# source_eagle.net
KiCad netlist of a schematic drawn in EAGLE
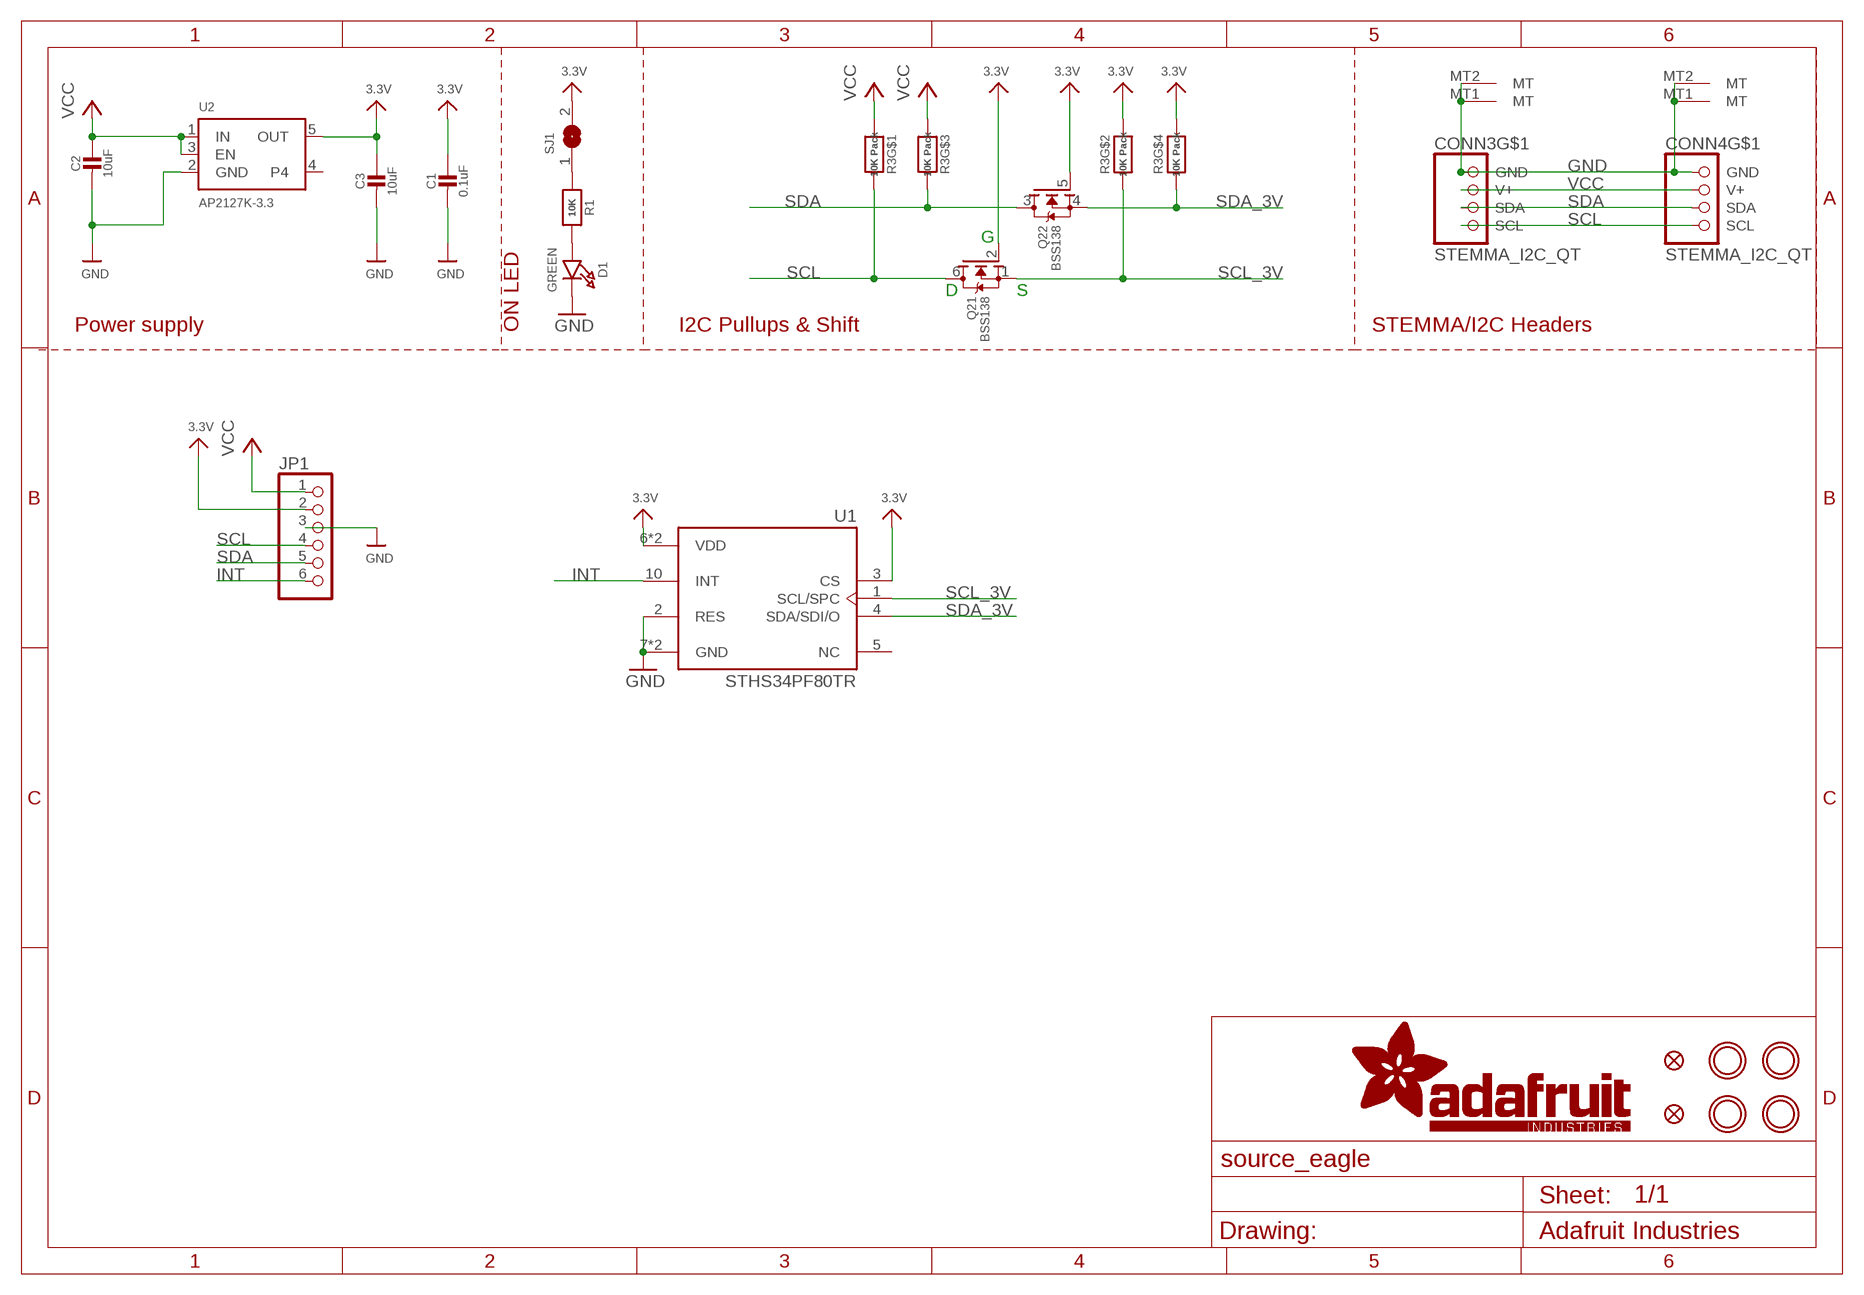
[diagram p0: schematic, sheet 1]

(export (version "E")
  (design (tool "Eeschema 10.0.6"))
  (components
    (comp (ref "C1")
      (value "0.1uF")
      (footprint "eagle-import:0603-NO")
      (libsource (lib "eagle-import") (part "CAP_CERAMIC0603_NO"))
    )
    (comp (ref "C2")
      (value "10uF")
      (footprint "eagle-import:0805-NO")
      (libsource (lib "eagle-import") (part "CAP_CERAMIC0805-NOOUTLINE"))
    )
    (comp (ref "C3")
      (value "10uF")
      (footprint "eagle-import:0805-NO")
      (libsource (lib "eagle-import") (part "CAP_CERAMIC0805-NOOUTLINE"))
    )
    (comp (ref "CONN3")
      (value "STEMMA_I2C_QT")
      (footprint "eagle-import:JST_SH4")
      (libsource (lib "eagle-import") (part "STEMMA_I2C_QT"))
    )
    (comp (ref "CONN4")
      (value "STEMMA_I2C_QT")
      (footprint "eagle-import:JST_SH4")
      (libsource (lib "eagle-import") (part "STEMMA_I2C_QT"))
    )
    (comp (ref "D1")
      (value "GREEN")
      (footprint "eagle-import:CHIPLED_0603_NOOUTLINE")
      (libsource (lib "eagle-import") (part "LED0603_NOOUTLINE"))
    )
    (comp (ref "FID3")
      (value "FIDUCIAL_0.5MM")
      (footprint "eagle-import:FIDUCIAL_0.5MM")
      (libsource (lib "eagle-import") (part "FIDUCIAL_0.5MM"))
    )
    (comp (ref "FID4")
      (value "FIDUCIAL_0.5MM")
      (footprint "eagle-import:FIDUCIAL_0.5MM")
      (libsource (lib "eagle-import") (part "FIDUCIAL_0.5MM"))
    )
    (comp (ref "JP1")
      (value "HEADER-1X670MIL")
      (footprint "eagle-import:1X06_ROUND_70")
      (libsource (lib "eagle-import") (part "HEADER-1X670MIL"))
    )
    (comp (ref "Q2")
      (value "BSS138")
      (footprint "eagle-import:SOT363")
      (libsource (lib "eagle-import") (part "MOSFET-N_DUAL"))
    )
    (comp (ref "R1")
      (value "10K")
      (footprint "eagle-import:0603-NO")
      (libsource (lib "eagle-import") (part "RESISTOR_0603_NOOUT"))
    )
    (comp (ref "R3")
      (value "10K Pack")
      (footprint "eagle-import:RESPACK_4X0603")
      (libsource (lib "eagle-import") (part "RESISTOR_4PACK"))
    )
    (comp (ref "SJ1")
      (value "SOLDERJUMPERCLOSED")
      (footprint "eagle-import:SOLDERJUMPER_CLOSEDWIRE")
      (libsource (lib "eagle-import") (part "SOLDERJUMPERCLOSED"))
    )
    (comp (ref "U$1")
      (value "MOUNTINGHOLE2.5")
      (footprint "eagle-import:MOUNTINGHOLE_2.5_PLATED")
      (libsource (lib "eagle-import") (part "MOUNTINGHOLE2.5"))
    )
    (comp (ref "U$17")
      (value "MOUNTINGHOLE2.5")
      (footprint "eagle-import:MOUNTINGHOLE_2.5_PLATED")
      (libsource (lib "eagle-import") (part "MOUNTINGHOLE2.5"))
    )
    (comp (ref "U$19")
      (value "MOUNTINGHOLE2.5")
      (footprint "eagle-import:MOUNTINGHOLE_2.5_PLATED")
      (libsource (lib "eagle-import") (part "MOUNTINGHOLE2.5"))
    )
    (comp (ref "U$21")
      (value "MOUNTINGHOLE2.5")
      (footprint "eagle-import:MOUNTINGHOLE_2.5_PLATED")
      (libsource (lib "eagle-import") (part "MOUNTINGHOLE2.5"))
    )
    (comp (ref "U1")
      (value "STHS34PF80TR")
      (footprint "eagle-import:XDCR_STHS34PF80TR")
      (fields (field (name "MANUFACTURER") "STmicroelectronics"))
      (libsource (lib "eagle-import") (part "STHS34PF80TR"))
    )
    (comp (ref "U2")
      (value "AP2127K-3.3")
      (footprint "eagle-import:SOT23-5")
      (libsource (lib "eagle-import") (part "VREG_SOT23-5"))
    )
  )
  (nets
    (net (code "1") (name "/INT") (class "Default")
      (node (ref "JP1") (pin "6") (pinfunction "6_6") (pintype "passive"))
      (node (ref "U1") (pin "10") (pinfunction "INT_10") (pintype "output"))
    )
    (net (code "2") (name "/SCL") (class "Default")
      (node (ref "CONN3") (pin "4") (pinfunction "SCL_4") (pintype "passive"))
      (node (ref "CONN4") (pin "4") (pinfunction "SCL_4") (pintype "passive"))
      (node (ref "JP1") (pin "4") (pinfunction "4_4") (pintype "passive"))
      (node (ref "Q2") (pin "6") (pinfunction "D_6") (pintype "bidirectional"))
      (node (ref "R3") (pin "8") (pinfunction "2_8") (pintype "passive"))
    )
    (net (code "3") (name "/SCL_3V") (class "Default")
      (node (ref "Q2") (pin "1") (pinfunction "S_1") (pintype "bidirectional"))
      (node (ref "R3") (pin "7") (pinfunction "2_7") (pintype "passive"))
      (node (ref "U1") (pin "1") (pinfunction "SCL/SPC_1") (pintype "input"))
    )
    (net (code "4") (name "/SDA") (class "Default")
      (node (ref "CONN3") (pin "3") (pinfunction "SDA_3") (pintype "passive"))
      (node (ref "CONN4") (pin "3") (pinfunction "SDA_3") (pintype "passive"))
      (node (ref "JP1") (pin "5") (pinfunction "5_5") (pintype "passive"))
      (node (ref "Q2") (pin "3") (pinfunction "D_3") (pintype "bidirectional"))
      (node (ref "R3") (pin "6") (pinfunction "2_6") (pintype "passive"))
    )
    (net (code "5") (name "/SDA_3V") (class "Default")
      (node (ref "Q2") (pin "4") (pinfunction "S_4") (pintype "bidirectional"))
      (node (ref "R3") (pin "5") (pinfunction "2_5") (pintype "passive"))
      (node (ref "U1") (pin "4") (pinfunction "SDA/SDI/O_4") (pintype "bidirectional"))
    )
    (net (code "6") (name "3.3V") (class "Default")
      (node (ref "C1") (pin "1") (pinfunction "1_1") (pintype "passive"))
      (node (ref "C3") (pin "1") (pinfunction "1_1") (pintype "passive"))
      (node (ref "JP1") (pin "2") (pinfunction "2_2") (pintype "passive"))
      (node (ref "Q2") (pin "2") (pinfunction "G_2") (pintype "bidirectional"))
      (node (ref "Q2") (pin "5") (pinfunction "G_5") (pintype "bidirectional"))
      (node (ref "R3") (pin "2") (pinfunction "1_2") (pintype "passive"))
      (node (ref "R3") (pin "4") (pinfunction "1_4") (pintype "passive"))
      (node (ref "SJ1") (pin "2") (pinfunction "2_2") (pintype "passive"))
      (node (ref "U1") (pin "3") (pinfunction "CS_3") (pintype "input"))
      (node (ref "U1") (pin "6") (pinfunction "VDD_6") (pintype "power_in"))
      (node (ref "U1") (pin "9") (pinfunction "VDD_9") (pintype "power_in"))
      (node (ref "U2") (pin "5") (pinfunction "OUT_5") (pintype "power_in"))
    )
    (net (code "7") (name "GND") (class "Default")
      (node (ref "C1") (pin "2") (pinfunction "2_2") (pintype "passive"))
      (node (ref "C2") (pin "2") (pinfunction "2_2") (pintype "passive"))
      (node (ref "C3") (pin "2") (pinfunction "2_2") (pintype "passive"))
      (node (ref "CONN3") (pin "1") (pinfunction "GND_1") (pintype "passive"))
      (node (ref "CONN3") (pin "MT1") (pinfunction "MT_MT1") (pintype "bidirectional"))
      (node (ref "CONN3") (pin "MT2") (pinfunction "MT_MT2") (pintype "bidirectional"))
      (node (ref "CONN4") (pin "1") (pinfunction "GND_1") (pintype "passive"))
      (node (ref "CONN4") (pin "MT1") (pinfunction "MT_MT1") (pintype "bidirectional"))
      (node (ref "CONN4") (pin "MT2") (pinfunction "MT_MT2") (pintype "bidirectional"))
      (node (ref "D1") (pin "C") (pinfunction "C_C") (pintype "passive"))
      (node (ref "JP1") (pin "3") (pinfunction "3_3") (pintype "passive"))
      (node (ref "U1") (pin "2") (pinfunction "RES_2") (pintype "passive"))
      (node (ref "U1") (pin "7") (pinfunction "GND_7") (pintype "power_in"))
      (node (ref "U1") (pin "8") (pinfunction "GND_8") (pintype "power_in"))
      (node (ref "U2") (pin "2") (pinfunction "GND_2") (pintype "power_in"))
    )
    (net (code "8") (name "Net-(D1-PadA)") (class "Default")
      (node (ref "D1") (pin "A") (pinfunction "A_A") (pintype "passive"))
      (node (ref "R1") (pin "2") (pinfunction "2_2") (pintype "passive"))
    )
    (net (code "9") (name "Net-(R1-Pad1)") (class "Default")
      (node (ref "R1") (pin "1") (pinfunction "1_1") (pintype "passive"))
      (node (ref "SJ1") (pin "1") (pinfunction "1_1") (pintype "passive"))
    )
    (net (code "10") (name "VCC") (class "Default")
      (node (ref "C2") (pin "1") (pinfunction "1_1") (pintype "passive"))
      (node (ref "CONN3") (pin "2") (pinfunction "V+_2") (pintype "passive"))
      (node (ref "CONN4") (pin "2") (pinfunction "V+_2") (pintype "passive"))
      (node (ref "JP1") (pin "1") (pinfunction "1_1") (pintype "passive"))
      (node (ref "R3") (pin "1") (pinfunction "1_1") (pintype "passive"))
      (node (ref "R3") (pin "3") (pinfunction "1_3") (pintype "passive"))
      (node (ref "U2") (pin "1") (pinfunction "IN_1") (pintype "power_in"))
      (node (ref "U2") (pin "3") (pinfunction "EN_3") (pintype "input"))
    )
    (net (code "11") (name "unconnected-(U1-NC-Pad5)") (class "Default")
      (node (ref "U1") (pin "5") (pinfunction "NC_5") (pintype "no_connect"))
    )
    (net (code "12") (name "unconnected-(U2-P4-Pad4)") (class "Default")
      (node (ref "U2") (pin "4") (pinfunction "P4_4") (pintype "bidirectional"))
    )
  )
)
